# Top_Sheet.net
KiCad netlist of a schematic drawn in Altium Designer
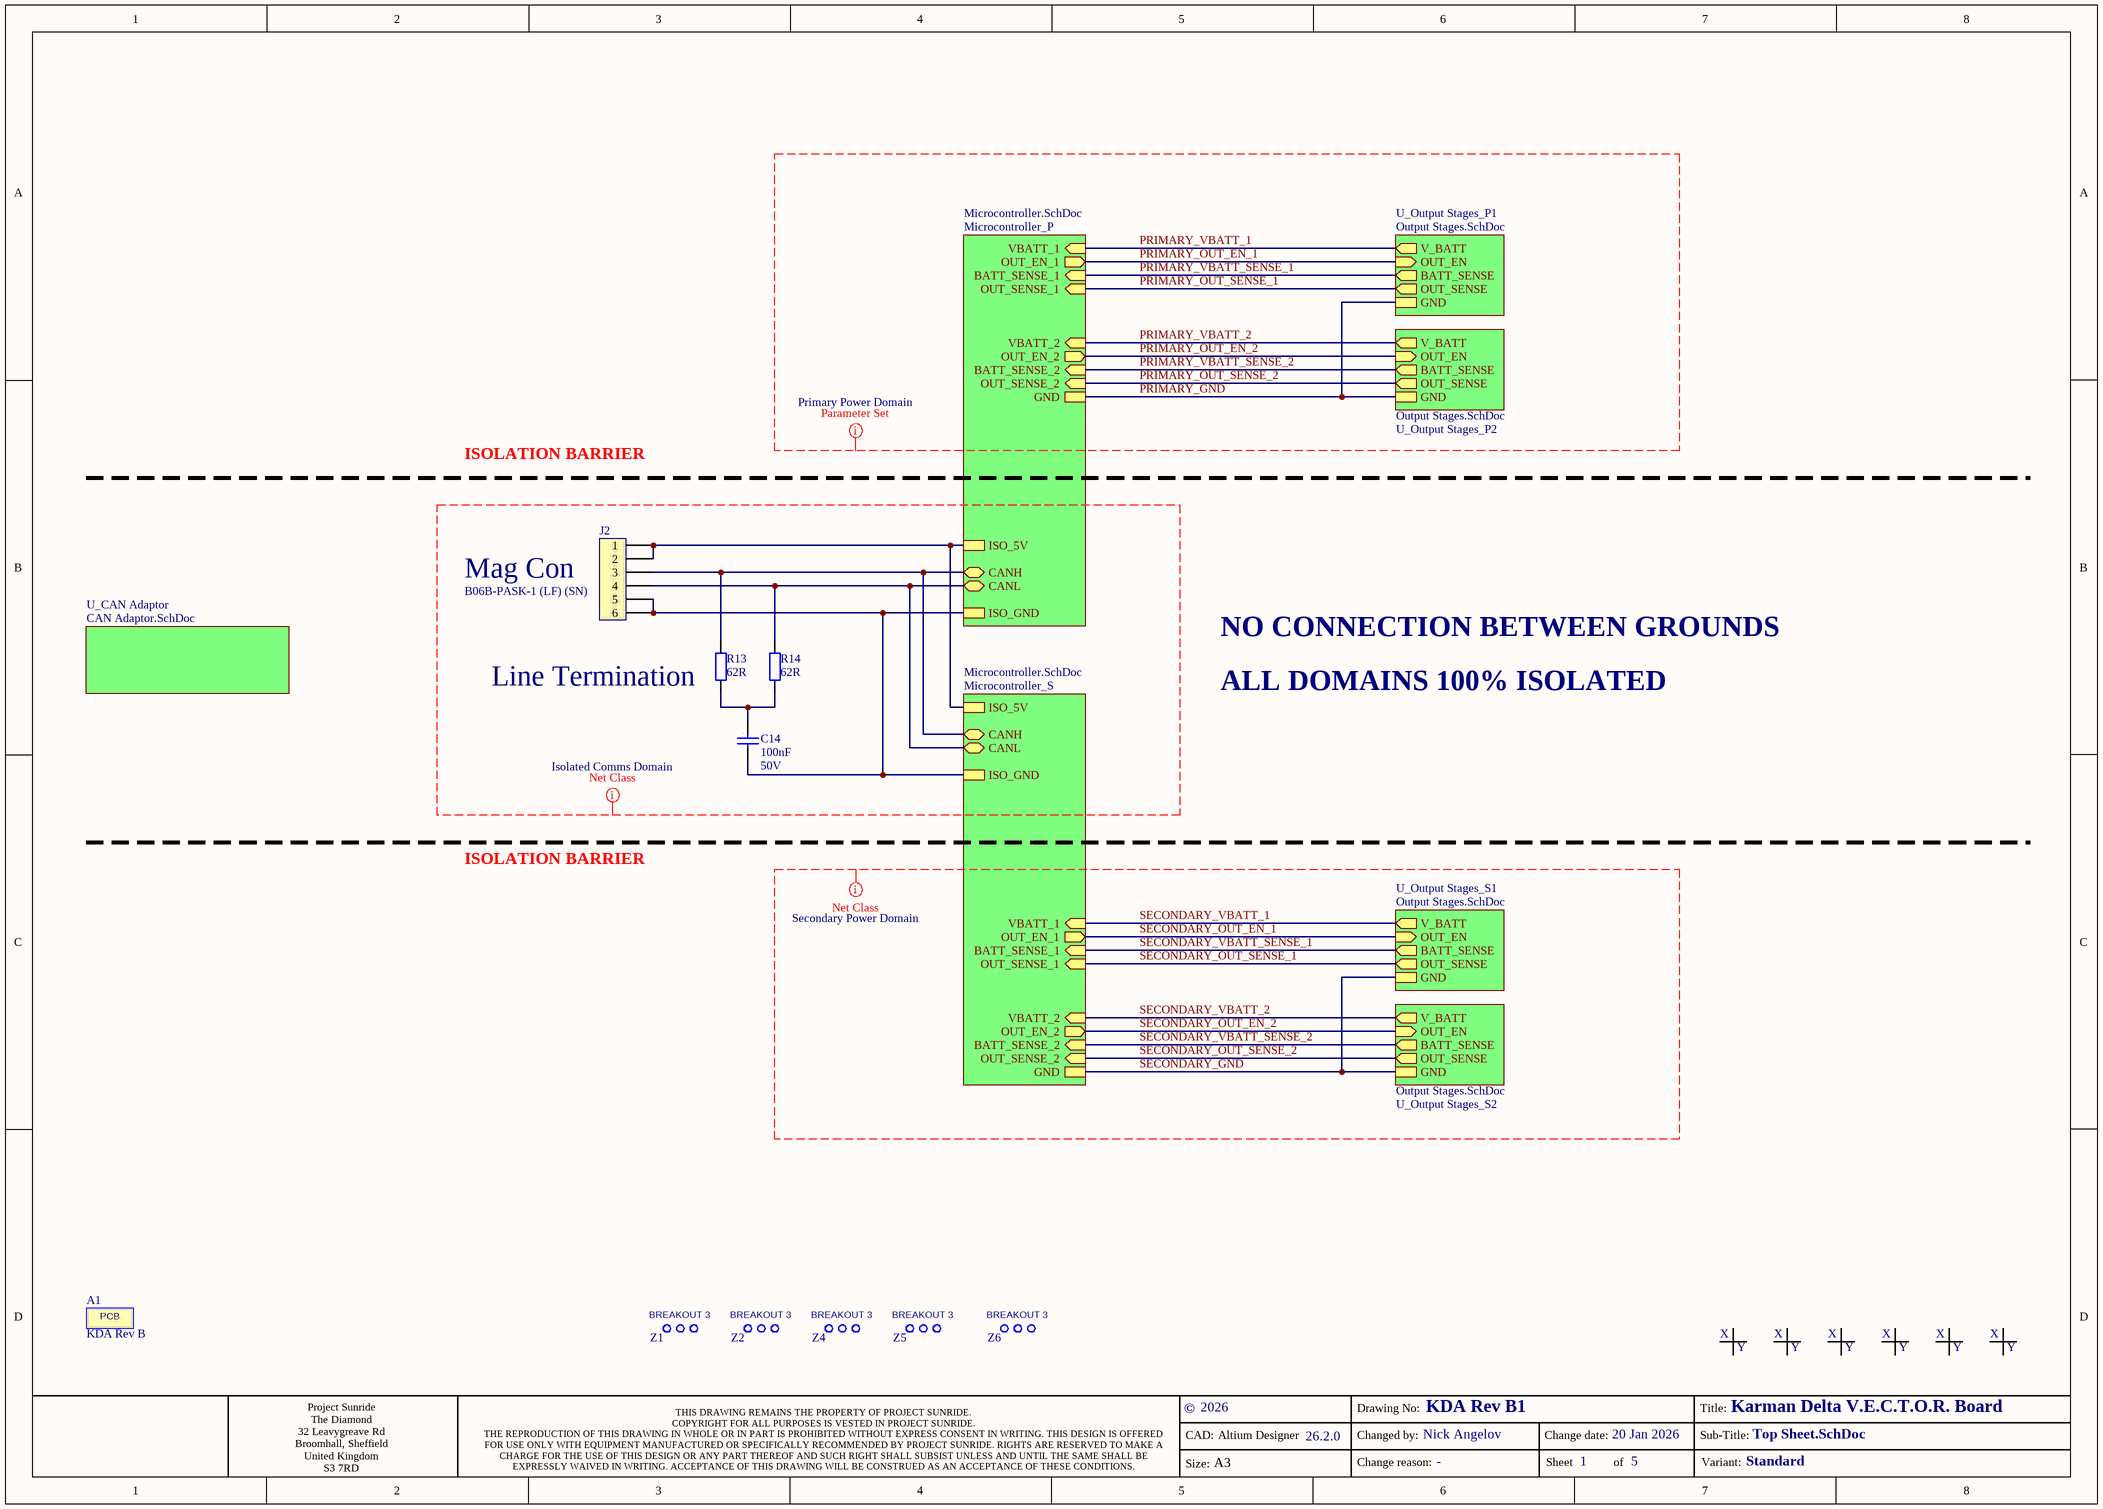
[diagram p0: Top Sheet.SchDoc]

(export (version "E")
  (design (tool "Eeschema 10.0.6"))
  (components
    (comp (ref "A1")
      (value "*")
      (footprint "PCB")
      (description "PCB (Bare Board)")
      (libsource (lib "Library") (part "PCB"))
    )
    (comp (ref "C14")
      (value "100nF")
      (footprint "CAPC1608X08L")
      (description "Capacitor MLC 100nF 50V X7R 10% CAPC1608X08M")
      (fields
        (field (name "VOLTAGE") "50V")
        (field (name "MANUFACTURER") "Murata")
        (field (name "MANUPARTNO") "GRM188R71H104KA93D")
      )
      (libsource (lib "Library") (part "CAP"))
    )
    (comp (ref "FID1")
      (value "*")
      (footprint "FIDRT")
      (description "Fiducial 1mm Dot Component Side")
      (libsource (lib "Library") (part "FID"))
    )
    (comp (ref "FID2")
      (value "*")
      (footprint "FIDRT")
      (description "Fiducial 1mm Dot Component Side")
      (libsource (lib "Library") (part "FID"))
    )
    (comp (ref "FID3")
      (value "*")
      (footprint "FIDRT")
      (description "Fiducial 1mm Dot Component Side")
      (libsource (lib "Library") (part "FID"))
    )
    (comp (ref "FID4")
      (value "*")
      (footprint "FIDRT")
      (description "Fiducial 1mm Dot Component Side")
      (libsource (lib "Library") (part "FID"))
    )
    (comp (ref "FID5")
      (value "*")
      (footprint "FIDRT")
      (description "Fiducial 1mm Dot Component Side")
      (libsource (lib "Library") (part "FID"))
    )
    (comp (ref "FID6")
      (value "*")
      (footprint "FIDRT")
      (description "Fiducial 1mm Dot Component Side")
      (libsource (lib "Library") (part "FID"))
    )
    (comp (ref "J2")
      (value "Mag Con")
      (footprint "B06B-PASK-1")
      (description "Connector 6 Way Vertical B06B-PASK-1 (LF) (SN) 2mm Pitch")
      (fields (field (name "MANUPARTNO") "B06B-PASK-1 (LF) (SN)") (field (name "MANUFACTURER") "JST"))
      (libsource (lib "Library") (part "CON6"))
    )
    (comp (ref "R13")
      (value "Line Termination")
      (footprint "RESC1608X06L")
      (description "SMD Chip Resistor, Thick Film, 62 ohm, 75V, 0603 [1608 Metric], 100mW, ± 1%, RC Series")
      (fields
        (field (name "ALTIUM_VALUE") "62R")
        (field (name "VOLTAGE") "75V")
        (field (name "POWER") "100mW")
      )
      (libsource (lib "Library") (part "RESISTOR"))
    )
    (comp (ref "R14")
      (value "62R")
      (footprint "RESC1608X06L")
      (description "SMD Chip Resistor, Thick Film, 62 ohm, 75V, 0603 [1608 Metric], 100mW, ± 1%, RC Series")
      (fields (field (name "VOLTAGE") "75V") (field (name "POWER") "100mW"))
      (libsource (lib "Library") (part "RESISTOR"))
    )
    (comp (ref "Z1")
      (value "*")
      (footprint "Breakout - 3 hole - short route")
      (description "Breakout - 3 hole - short route")
      (libsource (lib "Library") (part "Breakout - 3 hole"))
    )
    (comp (ref "Z2")
      (value "*")
      (footprint "Breakout - 3 hole - short route")
      (description "Breakout - 3 hole - short route")
      (libsource (lib "Library") (part "Breakout - 3 hole"))
    )
    (comp (ref "Z4")
      (value "*")
      (footprint "Breakout - 3 hole - short route")
      (description "Breakout - 3 hole - short route")
      (libsource (lib "Library") (part "Breakout - 3 hole"))
    )
    (comp (ref "Z5")
      (value "*")
      (footprint "Breakout - 3 hole - short route")
      (description "Breakout - 3 hole - short route")
      (libsource (lib "Library") (part "Breakout - 3 hole"))
    )
    (comp (ref "Z6")
      (value "*")
      (footprint "Breakout - 3 hole - short route")
      (description "Breakout - 3 hole - short route")
      (libsource (lib "Library") (part "Breakout - 3 hole"))
    )
  )
  (nets
    (net (code "1") (name "/CANH") (class "Default")
      (node (ref "J2") (pin "3") (pinfunction "3_3") (pintype "passive"))
      (node (ref "R13") (pin "2") (pinfunction "2_2") (pintype "passive"))
    )
    (net (code "2") (name "/CANL") (class "Default")
      (node (ref "J2") (pin "4") (pinfunction "4_4") (pintype "passive"))
      (node (ref "R14") (pin "2") (pinfunction "2_2") (pintype "passive"))
    )
    (net (code "3") (name "/ISO_5V") (class "Default")
      (node (ref "J2") (pin "1") (pinfunction "1_1") (pintype "passive"))
      (node (ref "J2") (pin "2") (pinfunction "2_2") (pintype "passive"))
    )
    (net (code "4") (name "/ISO_GND") (class "Default")
      (node (ref "C14") (pin "2") (pinfunction "2_2") (pintype "passive"))
      (node (ref "J2") (pin "5") (pinfunction "5_5") (pintype "passive"))
      (node (ref "J2") (pin "6") (pinfunction "6_6") (pintype "passive"))
    )
    (net (code "23") (name "Net-(C14-Pad1)") (class "Default")
      (node (ref "C14") (pin "1") (pinfunction "1_1") (pintype "passive"))
      (node (ref "R13") (pin "1") (pinfunction "1_1") (pintype "passive"))
      (node (ref "R14") (pin "1") (pinfunction "1_1") (pintype "passive"))
    )
  )
)
